# lpf_80.net
KiCad netlist of a schematic drawn in Altium Designer
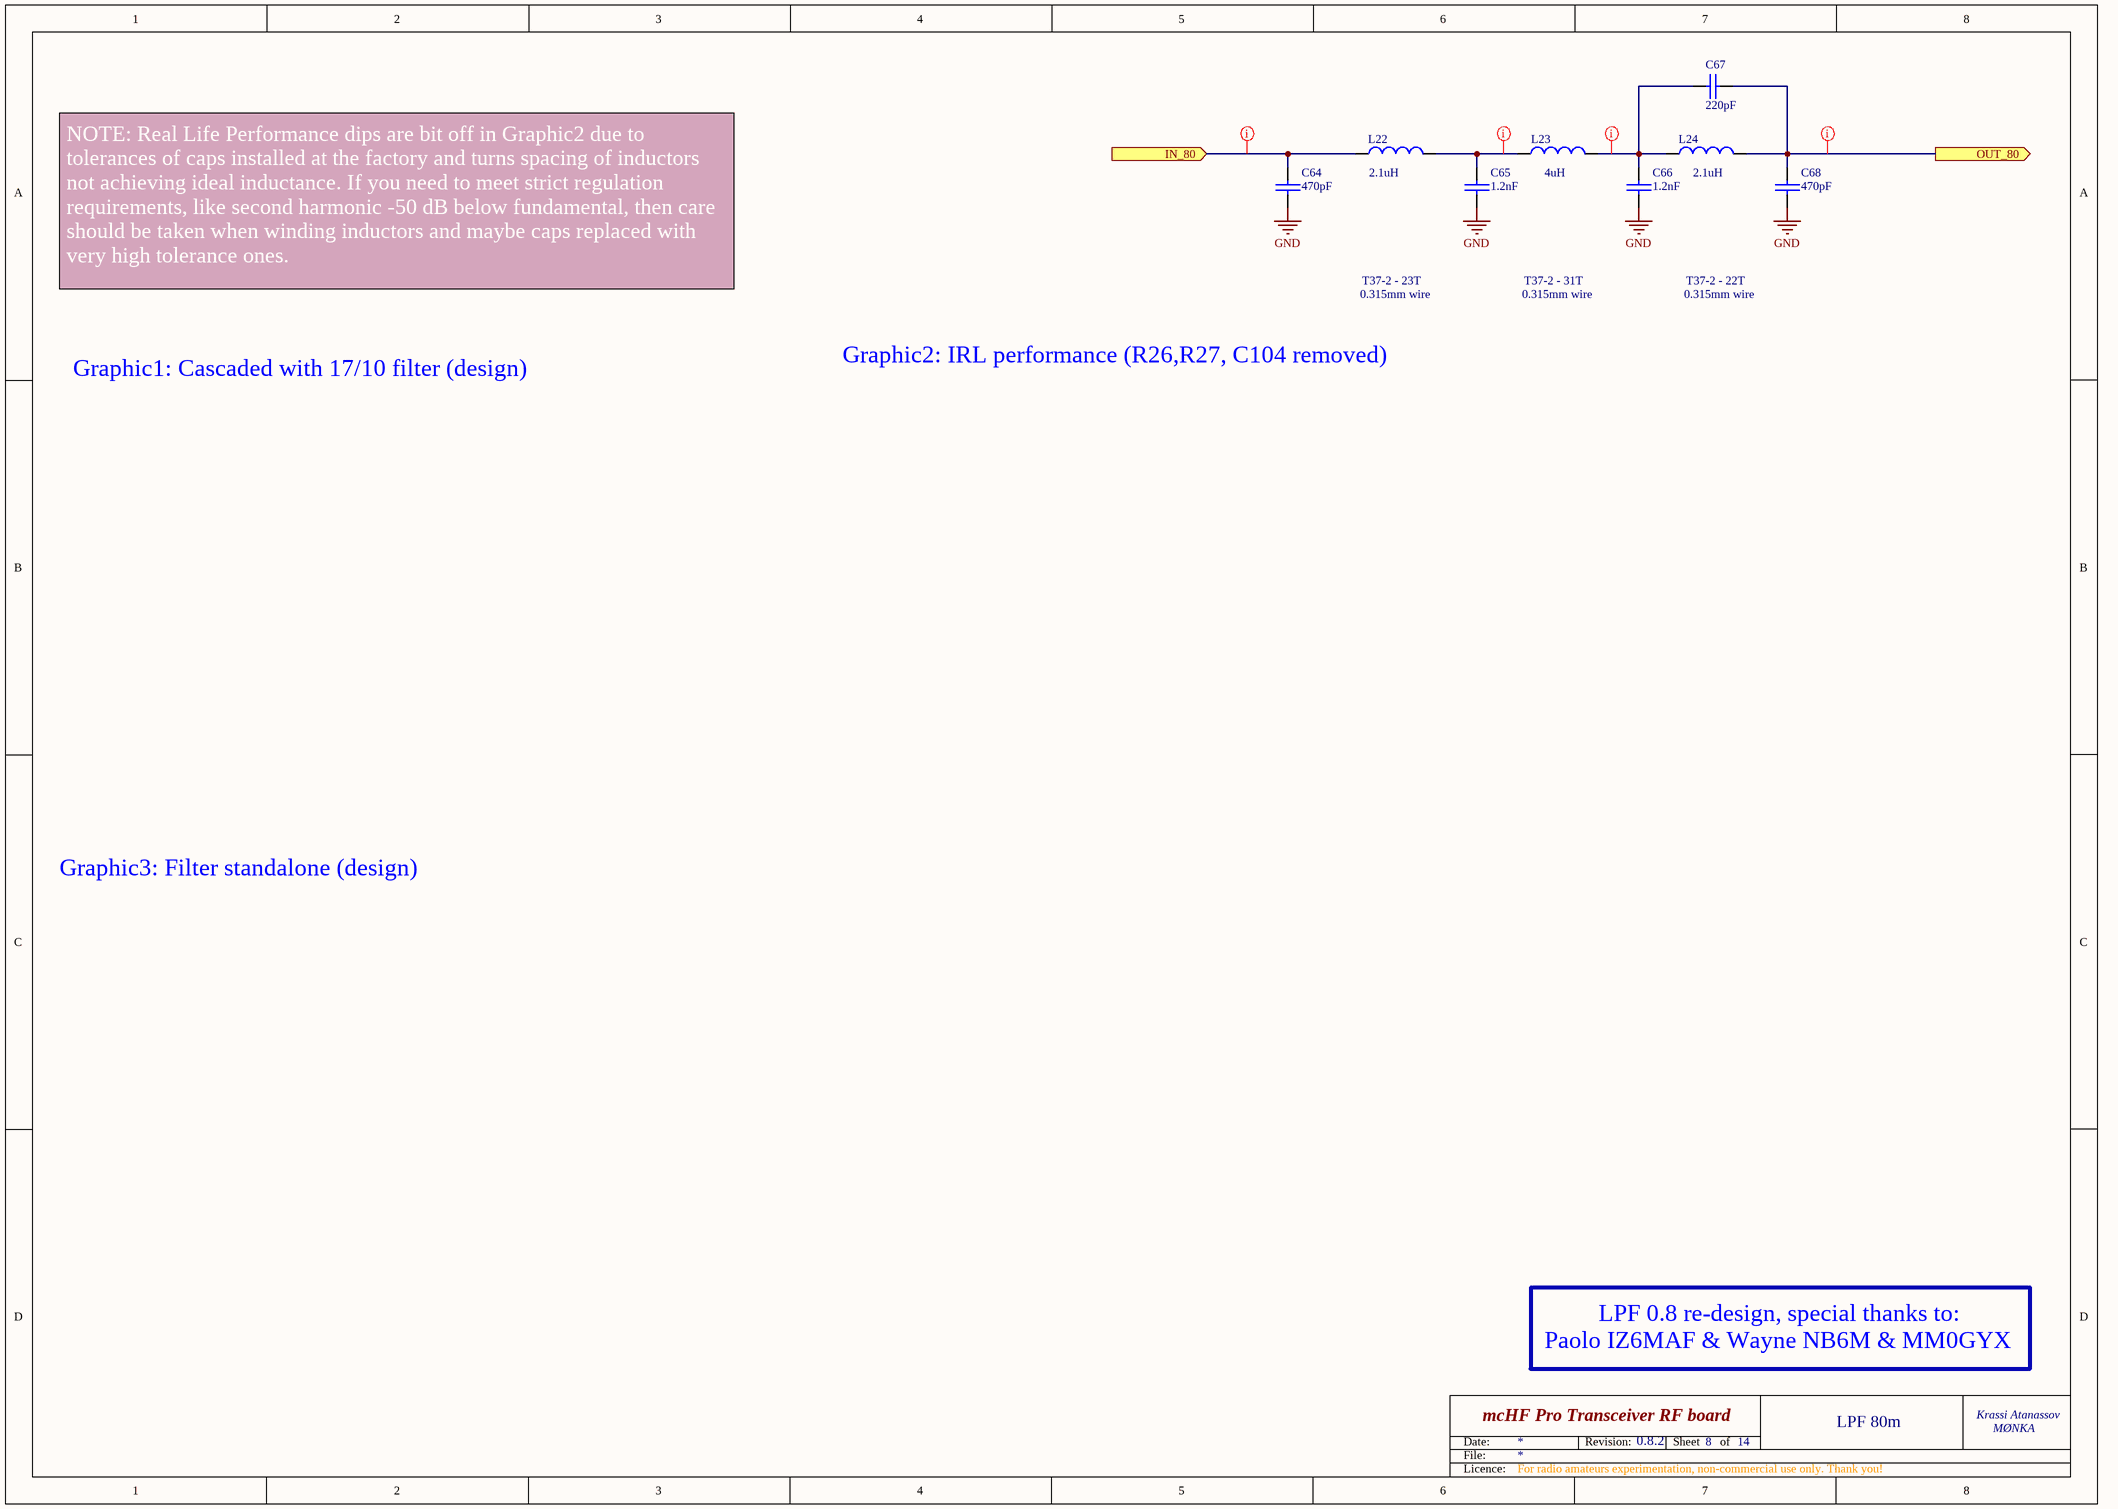
[diagram p0: lpf_80.SchDoc]

(export (version "E")
  (design (tool "Eeschema 10.0.6"))
  (components
    (comp (ref "C64")
      (value "470pF")
      (footprint "0805")
      (description "Capacitor")
      (fields (field (name "VOLTAGE") "100V"))
      (libsource (lib "mcHF_rf") (part "CAP"))
    )
    (comp (ref "C65")
      (value "1.2nF")
      (footprint "0805")
      (description "Capacitor")
      (fields (field (name "VOLTAGE") "100V"))
      (libsource (lib "mcHF_rf") (part "CAP"))
    )
    (comp (ref "C66")
      (value "1.2nF")
      (footprint "0805")
      (description "Capacitor")
      (fields (field (name "VOLTAGE") "100V"))
      (libsource (lib "mcHF_rf") (part "CAP"))
    )
    (comp (ref "C67")
      (value "220pF")
      (footprint "0805")
      (description "Capacitor")
      (fields (field (name "VOLTAGE") "100V"))
      (libsource (lib "mcHF_rf") (part "CAP"))
    )
    (comp (ref "C68")
      (value "470pF")
      (footprint "0805")
      (description "Capacitor")
      (fields (field (name "VOLTAGE") "100V"))
      (libsource (lib "mcHF_rf") (part "CAP"))
    )
    (comp (ref "L22")
      (value "T37-2")
      (footprint "LPF_IND")
      (description "T37-2 handwound inductor")
      (fields (field (name "INDUCTANCE") "2.1uH"))
      (libsource (lib "mcHF_rf") (part "LPF_IND"))
    )
    (comp (ref "L23")
      (value "T37-2")
      (footprint "LPF_IND")
      (description "T37-2 handwound inductor")
      (fields (field (name "INDUCTANCE") "4uH"))
      (libsource (lib "mcHF_rf") (part "LPF_IND"))
    )
    (comp (ref "L24")
      (value "T37-2")
      (footprint "LPF_IND")
      (description "T37-2 handwound inductor")
      (fields (field (name "INDUCTANCE") "2.1uH"))
      (libsource (lib "mcHF_rf") (part "LPF_IND"))
    )
  )
  (nets
    (net (code "1") (name "/IN_80") (class "Default")
      (node (ref "C64") (pin "1") (pinfunction "1_1") (pintype "passive"))
      (node (ref "L22") (pin "1") (pinfunction "1_1") (pintype "passive"))
    )
    (net (code "2") (name "/OUT_80") (class "Default")
      (node (ref "C67") (pin "1") (pinfunction "1_1") (pintype "passive"))
      (node (ref "C68") (pin "1") (pinfunction "1_1") (pintype "passive"))
      (node (ref "L24") (pin "2") (pinfunction "2_2") (pintype "passive"))
    )
    (net (code "3") (name "GND") (class "Default")
      (node (ref "C64") (pin "2") (pinfunction "2_2") (pintype "passive"))
      (node (ref "C65") (pin "2") (pinfunction "2_2") (pintype "passive"))
      (node (ref "C66") (pin "2") (pinfunction "2_2") (pintype "passive"))
      (node (ref "C68") (pin "2") (pinfunction "2_2") (pintype "passive"))
    )
    (net (code "4") (name "Net-(C65-Pad1)") (class "Default")
      (node (ref "C65") (pin "1") (pinfunction "1_1") (pintype "passive"))
      (node (ref "L22") (pin "2") (pinfunction "2_2") (pintype "passive"))
      (node (ref "L23") (pin "1") (pinfunction "1_1") (pintype "passive"))
    )
    (net (code "5") (name "Net-(C66-Pad1)") (class "Default")
      (node (ref "C66") (pin "1") (pinfunction "1_1") (pintype "passive"))
      (node (ref "C67") (pin "2") (pinfunction "2_2") (pintype "passive"))
      (node (ref "L23") (pin "2") (pinfunction "2_2") (pintype "passive"))
      (node (ref "L24") (pin "1") (pinfunction "1_1") (pintype "passive"))
    )
  )
)
